# H01R0_Frontend.net
KiCad netlist of a schematic drawn in Altium Designer
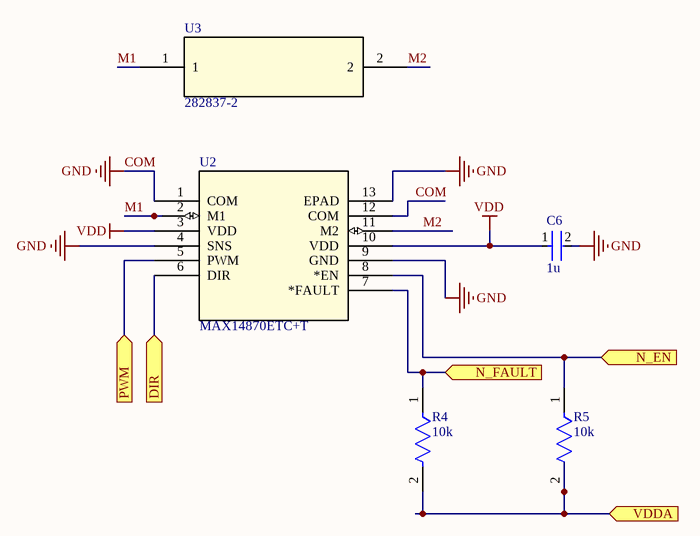
[diagram p0: H01R0_Frontend.SchDoc]

(export (version "E")
  (design (tool "Eeschema 10.0.6"))
  (components
    (comp (ref "C6")
      (value "1u")
      (footprint "FP-0603-L_1_6_0_15-W_0_8-IPC_C")
      (description "Ceramic Capacitor General Use 1uF ±10% 50V X7R 0603")
      (fields (field (name "TOLERANCE") "10%"))
      (libsource (lib "Altium Content Vault") (part "11868f565c42a9108669ba33697ecf6"))
    )
    (comp (ref "R4")
      (value "10k")
      (footprint "FP-SG73P1J-MFG")
      (description "SG73P1JTTD1002F Res Thick Film 0603 10K Ohm 1% 0.2W(1/5W) ±100ppm/C Pad SMD Automotive T/R")
      (fields (field (name "TOLERANCE") "1%"))
      (libsource (lib "Altium Content Vault") (part "1029c3af85768c4190bb7ad29bc67b5"))
    )
    (comp (ref "R5")
      (value "10k")
      (footprint "FP-SG73P1J-MFG")
      (description "SG73P1JTTD1002F Res Thick Film 0603 10K Ohm 1% 0.2W(1/5W) ±100ppm/C Pad SMD Automotive T/R")
      (fields (field (name "TOLERANCE") "1%"))
      (libsource (lib "Altium Content Vault") (part "1029c3af85768c4190bb7ad29bc67b5"))
    )
    (comp (ref "U2")
      (value "MAX14870ETC+T")
      (footprint "MAX14870ETC&plus_T:21-0664B_MXM")
      (description "Compact 4.5V to 36V Full-Bridge DC Motor Drivers")
      (fields (field (name "COPYRIGHT") "Copyright (C) 2025 Ultra Librarian. All rights reserved."))
      (libsource (lib "MAX14870ETC&plus_T") (part "MAX14870ETC+T"))
    )
    (comp (ref "U3")
      (value "282837-2")
      (footprint "282837-2_TYC")
      (description "TERMI-BLOK PCB MOUNT 2P")
      (fields (field (name "COPYRIGHT") "Copyright (C) 2025 Ultra Librarian. All rights reserved."))
      (libsource (lib "Nate Fischer") (part "282837-2"))
    )
  )
  (nets
    (net (code "1") (name "/  N_FAULT") (class "Default")
      (node (ref "R4") (pin "1") (pinfunction "1_1") (pintype "passive"))
      (node (ref "U2") (pin "7") (pinfunction "*FAULT_7") (pintype "passive"))
    )
    (net (code "2") (name "/DIR") (class "Default")
      (node (ref "U2") (pin "6") (pinfunction "DIR_6") (pintype "passive"))
    )
    (net (code "3") (name "/M1") (class "Default")
      (node (ref "U2") (pin "2") (pinfunction "M1_2") (pintype "bidirectional"))
      (node (ref "U3") (pin "1") (pinfunction "1_1") (pintype "passive"))
    )
    (net (code "4") (name "/M2") (class "Default")
      (node (ref "U2") (pin "11") (pinfunction "M2_11") (pintype "bidirectional"))
      (node (ref "U3") (pin "2") (pinfunction "2_2") (pintype "passive"))
    )
    (net (code "5") (name "/N_EN") (class "Default")
      (node (ref "R5") (pin "1") (pinfunction "1_1") (pintype "passive"))
      (node (ref "U2") (pin "8") (pinfunction "*EN_8") (pintype "passive"))
    )
    (net (code "6") (name "/PWM") (class "Default")
      (node (ref "U2") (pin "5") (pinfunction "PWM_5") (pintype "passive"))
    )
    (net (code "7") (name "/VDDA") (class "Default")
      (node (ref "R4") (pin "2") (pinfunction "2_2") (pintype "passive"))
      (node (ref "R5") (pin "2") (pinfunction "2_2") (pintype "passive"))
    )
    (net (code "8") (name "GND") (class "Default")
      (node (ref "C6") (pin "2") (pinfunction "2_2") (pintype "passive"))
      (node (ref "U2") (pin "1") (pinfunction "COM_1") (pintype "passive"))
      (node (ref "U2") (pin "12") (pinfunction "COM_12") (pintype "passive"))
      (node (ref "U2") (pin "13") (pinfunction "EPAD_13") (pintype "passive"))
      (node (ref "U2") (pin "4") (pinfunction "SNS_4") (pintype "passive"))
      (node (ref "U2") (pin "9") (pinfunction "GND_9") (pintype "power_in"))
    )
    (net (code "9") (name "VDD") (class "Default")
      (node (ref "C6") (pin "1") (pinfunction "1_1") (pintype "passive"))
      (node (ref "U2") (pin "10") (pinfunction "VDD_10") (pintype "power_in"))
      (node (ref "U2") (pin "3") (pinfunction "VDD_3") (pintype "power_in"))
    )
  )
)
